# ssslidar_v0_1_main_board.net
KiCad netlist of a schematic drawn in EAGLE
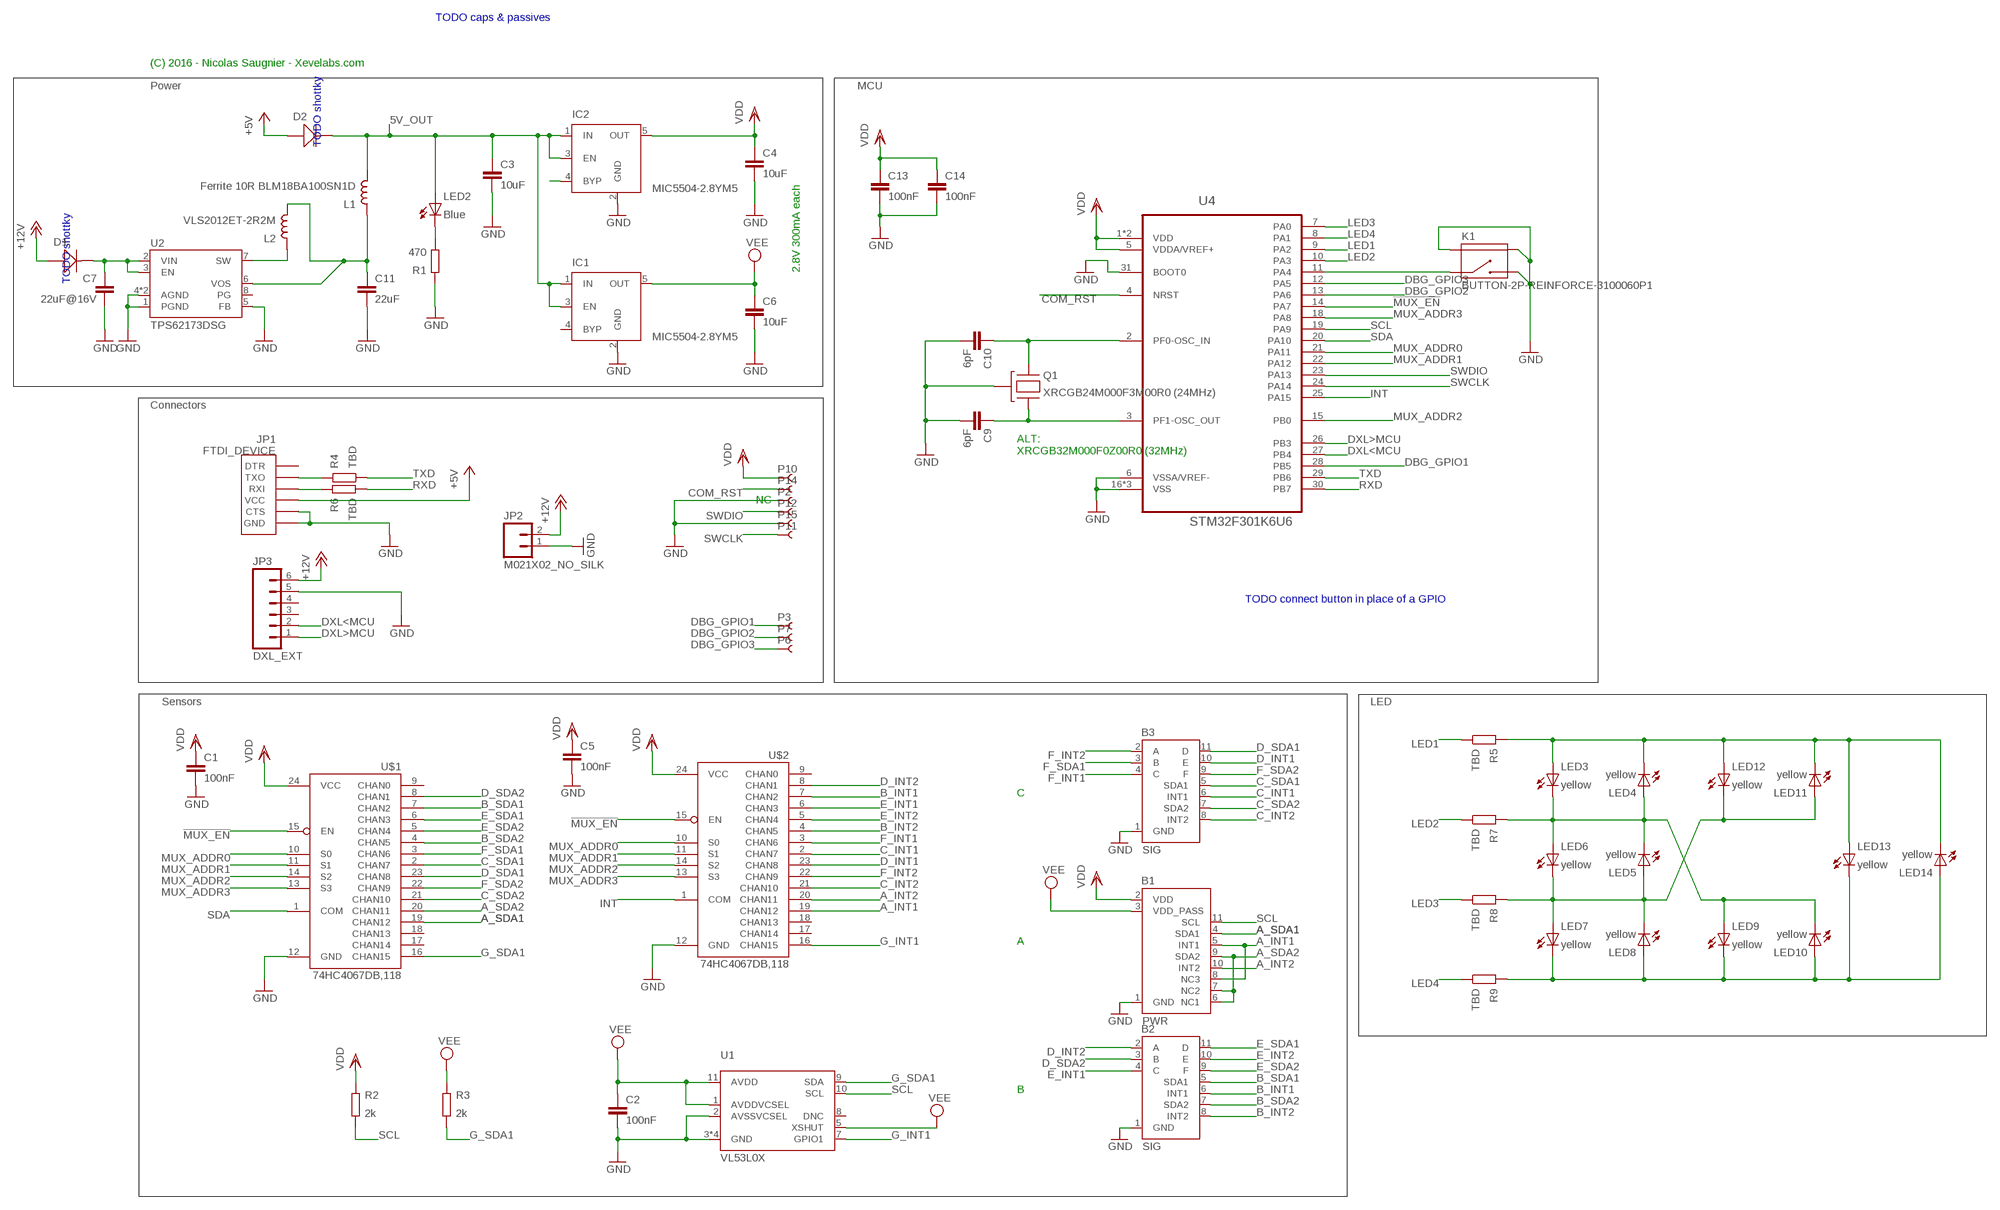
[diagram p0: schematic, sheet 1]

(export (version "E")
  (design (tool "Eeschema 10.0.6"))
  (components
    (comp (ref "B1")
      (value "PWR")
      (footprint "eagle-import:BLADE")
      (libsource (lib "eagle-import") (part "BLADE_PWR_BOTTOM"))
    )
    (comp (ref "B2")
      (value "SIG")
      (footprint "eagle-import:BLADE")
      (libsource (lib "eagle-import") (part "BLADE_SIG_BOTTOM"))
    )
    (comp (ref "B3")
      (value "SIG")
      (footprint "eagle-import:BLADE")
      (libsource (lib "eagle-import") (part "BLADE_SIG_BOTTOM"))
    )
    (comp (ref "C1")
      (value "100nF")
      (footprint "eagle-import:0402_N")
      (libsource (lib "eagle-import") (part "C0402"))
    )
    (comp (ref "C2")
      (value "100nF")
      (footprint "eagle-import:0402_N")
      (libsource (lib "eagle-import") (part "C0402"))
    )
    (comp (ref "C3")
      (value "10uF")
      (footprint "eagle-import:0805_N")
      (libsource (lib "eagle-import") (part "C0805"))
    )
    (comp (ref "C4")
      (value "10uF")
      (footprint "eagle-import:0805_N")
      (libsource (lib "eagle-import") (part "C0805"))
    )
    (comp (ref "C5")
      (value "100nF")
      (footprint "eagle-import:0402_N")
      (libsource (lib "eagle-import") (part "C0402"))
    )
    (comp (ref "C6")
      (value "10uF")
      (footprint "eagle-import:0805_N")
      (libsource (lib "eagle-import") (part "C0805"))
    )
    (comp (ref "C7")
      (value "22uF@16V")
      (footprint "eagle-import:1206_L")
      (libsource (lib "eagle-import") (part "C1206_L"))
    )
    (comp (ref "C9")
      (value "6pF")
      (footprint "eagle-import:0402_N")
      (libsource (lib "eagle-import") (part "C0402"))
    )
    (comp (ref "C10")
      (value "6pF")
      (footprint "eagle-import:0402_N")
      (libsource (lib "eagle-import") (part "C0402"))
    )
    (comp (ref "C11")
      (value "22uF")
      (footprint "eagle-import:1206_L")
      (libsource (lib "eagle-import") (part "C1206_L"))
    )
    (comp (ref "C13")
      (value "100nF")
      (footprint "eagle-import:0402_N")
      (libsource (lib "eagle-import") (part "C0402"))
    )
    (comp (ref "C14")
      (value "100nF")
      (footprint "eagle-import:0402_N")
      (libsource (lib "eagle-import") (part "C0402"))
    )
    (comp (ref "D1")
      (value "D-SOD-123")
      (footprint "eagle-import:SOD123")
      (libsource (lib "eagle-import") (part "D-SOD-123"))
    )
    (comp (ref "D2")
      (value "D-SOD-123")
      (footprint "eagle-import:SOD123")
      (libsource (lib "eagle-import") (part "D-SOD-123"))
    )
    (comp (ref "IC1")
      (value "MIC5504-2.8YM5")
      (footprint "eagle-import:SOT23-5")
      (libsource (lib "eagle-import") (part "MIC5219XX"))
    )
    (comp (ref "IC2")
      (value "MIC5504-2.8YM5")
      (footprint "eagle-import:SOT23-5")
      (libsource (lib "eagle-import") (part "MIC5219XX"))
    )
    (comp (ref "JP1")
      (value "FTDI_DEVICE")
      (footprint "eagle-import:FTDI_DEVICE_SIDE")
      (libsource (lib "eagle-import") (part "FTDI_DEVICE"))
    )
    (comp (ref "JP2")
      (value "M021X02_NO_SILK")
      (footprint "eagle-import:1X02_NO_SILK")
      (libsource (lib "eagle-import") (part "M021X02_NO_SILK"))
    )
    (comp (ref "JP3")
      (value "DXL_EXT")
      (footprint "eagle-import:1X06-1.27MM")
      (libsource (lib "eagle-import") (part "M061.27MM"))
    )
    (comp (ref "K1")
      (value "BUTTON-2P-REINFORCE-3100060P1")
      (footprint "eagle-import:4P-SMD-7.0X3.5X3.5H-90D")
      (libsource (lib "eagle-import") (part "BUTTON-2P-REINFORCE-3100060P1"))
    )
    (comp (ref "L1")
      (value "Ferrite 10R BLM18BA100SN1D")
      (footprint "eagle-import:0603_N")
      (libsource (lib "eagle-import") (part "L0603"))
    )
    (comp (ref "L2")
      (value "VLS2012ET-2R2M")
      (footprint "eagle-import:2016_METRIC_N")
      (libsource (lib "eagle-import") (part "L2016M"))
    )
    (comp (ref "LED2")
      (value "Blue")
      (footprint "eagle-import:D_0603_N")
      (libsource (lib "eagle-import") (part "LED0603"))
    )
    (comp (ref "LED3")
      (value "yellow")
      (footprint "eagle-import:D_0603_N")
      (libsource (lib "eagle-import") (part "LED0603"))
    )
    (comp (ref "LED4")
      (value "yellow")
      (footprint "eagle-import:D_0603_N")
      (libsource (lib "eagle-import") (part "LED0603"))
    )
    (comp (ref "LED5")
      (value "yellow")
      (footprint "eagle-import:D_0603_N")
      (libsource (lib "eagle-import") (part "LED0603"))
    )
    (comp (ref "LED6")
      (value "yellow")
      (footprint "eagle-import:D_0603_N")
      (libsource (lib "eagle-import") (part "LED0603"))
    )
    (comp (ref "LED7")
      (value "yellow")
      (footprint "eagle-import:D_0603_N")
      (libsource (lib "eagle-import") (part "LED0603"))
    )
    (comp (ref "LED8")
      (value "yellow")
      (footprint "eagle-import:D_0603_N")
      (libsource (lib "eagle-import") (part "LED0603"))
    )
    (comp (ref "LED9")
      (value "yellow")
      (footprint "eagle-import:D_0603_N")
      (libsource (lib "eagle-import") (part "LED0603"))
    )
    (comp (ref "LED10")
      (value "yellow")
      (footprint "eagle-import:D_0603_N")
      (libsource (lib "eagle-import") (part "LED0603"))
    )
    (comp (ref "LED11")
      (value "yellow")
      (footprint "eagle-import:D_0603_N")
      (libsource (lib "eagle-import") (part "LED0603"))
    )
    (comp (ref "LED12")
      (value "yellow")
      (footprint "eagle-import:D_0603_N")
      (libsource (lib "eagle-import") (part "LED0603"))
    )
    (comp (ref "LED13")
      (value "yellow")
      (footprint "eagle-import:D_0603_N")
      (libsource (lib "eagle-import") (part "LED0603"))
    )
    (comp (ref "LED14")
      (value "yellow")
      (footprint "eagle-import:D_0603_N")
      (libsource (lib "eagle-import") (part "LED0603"))
    )
    (comp (ref "P2")
      (value "PIN_SMD_1X1.6")
      (footprint "eagle-import:PIN_SMD_1X1.6")
      (libsource (lib "eagle-import") (part "PIN_SMD_1X1.6"))
    )
    (comp (ref "P3")
      (value "PIN_SMD_1X1")
      (footprint "eagle-import:PIN_SMD_1X1")
      (libsource (lib "eagle-import") (part "PIN_SMD_1X1"))
    )
    (comp (ref "P6")
      (value "PIN_SMD_1X1")
      (footprint "eagle-import:PIN_SMD_1X1")
      (libsource (lib "eagle-import") (part "PIN_SMD_1X1"))
    )
    (comp (ref "P7")
      (value "PIN_SMD_1X1")
      (footprint "eagle-import:PIN_SMD_1X1")
      (libsource (lib "eagle-import") (part "PIN_SMD_1X1"))
    )
    (comp (ref "P10")
      (value "PIN_SMD_1X1.6")
      (footprint "eagle-import:PIN_SMD_1X1.6")
      (libsource (lib "eagle-import") (part "PIN_SMD_1X1.6"))
    )
    (comp (ref "P11")
      (value "PIN_SMD_1X1.6")
      (footprint "eagle-import:PIN_SMD_1X1.6")
      (libsource (lib "eagle-import") (part "PIN_SMD_1X1.6"))
    )
    (comp (ref "P12")
      (value "PIN_SMD_1X1.6")
      (footprint "eagle-import:PIN_SMD_1X1.6")
      (libsource (lib "eagle-import") (part "PIN_SMD_1X1.6"))
    )
    (comp (ref "P14")
      (value "PIN_SMD_1X1.6")
      (footprint "eagle-import:PIN_SMD_1X1.6")
      (libsource (lib "eagle-import") (part "PIN_SMD_1X1.6"))
    )
    (comp (ref "P15")
      (value "PIN_SMD_1X1.6")
      (footprint "eagle-import:PIN_SMD_1X1.6")
      (libsource (lib "eagle-import") (part "PIN_SMD_1X1.6"))
    )
    (comp (ref "Q1")
      (value "XRCGB24M000F3M00R0 (24MHz)")
      (footprint "eagle-import:CRYSTAL_2.0X1.6_4P")
      (libsource (lib "eagle-import") (part "CRYSTAL_W/BODY-2.0X1.6"))
    )
    (comp (ref "R1")
      (value "470")
      (footprint "eagle-import:0402_N")
      (libsource (lib "eagle-import") (part "R0402"))
    )
    (comp (ref "R2")
      (value "2k")
      (footprint "eagle-import:0402_N")
      (libsource (lib "eagle-import") (part "R0402"))
    )
    (comp (ref "R3")
      (value "2k")
      (footprint "eagle-import:0402_N")
      (libsource (lib "eagle-import") (part "R0402"))
    )
    (comp (ref "R4")
      (value "TBD")
      (footprint "eagle-import:0402_N")
      (libsource (lib "eagle-import") (part "R0402"))
    )
    (comp (ref "R5")
      (value "TBD")
      (footprint "eagle-import:0402_N")
      (libsource (lib "eagle-import") (part "R0402"))
    )
    (comp (ref "R6")
      (value "TBD")
      (footprint "eagle-import:0402_N")
      (libsource (lib "eagle-import") (part "R0402"))
    )
    (comp (ref "R7")
      (value "TBD")
      (footprint "eagle-import:0402_N")
      (libsource (lib "eagle-import") (part "R0402"))
    )
    (comp (ref "R8")
      (value "TBD")
      (footprint "eagle-import:0402_N")
      (libsource (lib "eagle-import") (part "R0402"))
    )
    (comp (ref "R9")
      (value "TBD")
      (footprint "eagle-import:0402_N")
      (libsource (lib "eagle-import") (part "R0402"))
    )
    (comp (ref "U$1")
      (value "74HC4067DB,118")
      (footprint "eagle-import:SSOP24")
      (libsource (lib "eagle-import") (part "MUX-74HC4067SMD"))
    )
    (comp (ref "U$2")
      (value "74HC4067DB,118")
      (footprint "eagle-import:SSOP24")
      (libsource (lib "eagle-import") (part "MUX-74HC4067SMD"))
    )
    (comp (ref "U1")
      (value "VL53L0X")
      (footprint "eagle-import:VL53L0X")
      (libsource (lib "eagle-import") (part "VL53L0X"))
    )
    (comp (ref "U2")
      (value "TPS62173DSG")
      (footprint "eagle-import:SON50P200X200X80-9N")
      (libsource (lib "eagle-import") (part "IC_TPS62160DSG_N"))
    )
    (comp (ref "U4")
      (value "STM32F301K6U6")
      (footprint "eagle-import:QFN50P500X500X60-33N")
      (fields (field (name "MPN") "STM32F050K4U6A"))
      (libsource (lib "eagle-import") (part "STM32F301K6U6"))
    )
  )
  (nets
    (net (code "1") (name "+5V") (class "Default")
      (node (ref "D2") (pin "+") (pinfunction "+_+") (pintype "passive"))
      (node (ref "JP1") (pin "P$4") (pinfunction "VCC_P$4") (pintype "bidirectional"))
    )
    (net (code "2") (name "+12V") (class "Default")
      (node (ref "D1") (pin "+") (pinfunction "+_+") (pintype "passive"))
      (node (ref "JP2") (pin "2") (pinfunction "2_2") (pintype "passive"))
      (node (ref "JP3") (pin "6") (pinfunction "6_6") (pintype "passive"))
    )
    (net (code "3") (name "/5V_OUT") (class "Default")
      (node (ref "C3") (pin "1") (pinfunction "1_1") (pintype "passive"))
      (node (ref "D2") (pin "-") (pinfunction "-_-") (pintype "passive"))
      (node (ref "IC1") (pin "1") (pinfunction "IN_1") (pintype "input"))
      (node (ref "IC1") (pin "3") (pinfunction "EN_3") (pintype "input"))
      (node (ref "IC2") (pin "1") (pinfunction "IN_1") (pintype "input"))
      (node (ref "IC2") (pin "3") (pinfunction "EN_3") (pintype "input"))
      (node (ref "L1") (pin "2") (pinfunction "2_2") (pintype "passive"))
      (node (ref "LED2") (pin "A") (pinfunction "A_A") (pintype "passive"))
    )
    (net (code "4") (name "/A_INT1") (class "Default")
      (node (ref "B1") (pin "5") (pinfunction "INT1_5") (pintype "bidirectional"))
      (node (ref "B1") (pin "8") (pinfunction "NC3_8") (pintype "bidirectional"))
      (node (ref "U$2") (pin "19") (pinfunction "CHAN12_19") (pintype "bidirectional"))
    )
    (net (code "5") (name "/A_INT2") (class "Default")
      (node (ref "B1") (pin "10") (pinfunction "INT2_10") (pintype "bidirectional"))
      (node (ref "U$2") (pin "20") (pinfunction "CHAN11_20") (pintype "bidirectional"))
    )
    (net (code "6") (name "/A_SDA1") (class "Default")
      (node (ref "B1") (pin "4") (pinfunction "SDA1_4") (pintype "bidirectional"))
      (node (ref "U$1") (pin "19") (pinfunction "CHAN12_19") (pintype "bidirectional"))
    )
    (net (code "7") (name "/A_SDA2") (class "Default")
      (node (ref "B1") (pin "6") (pinfunction "NC1_6") (pintype "bidirectional"))
      (node (ref "B1") (pin "7") (pinfunction "NC2_7") (pintype "bidirectional"))
      (node (ref "B1") (pin "9") (pinfunction "SDA2_9") (pintype "bidirectional"))
      (node (ref "U$1") (pin "20") (pinfunction "CHAN11_20") (pintype "bidirectional"))
    )
    (net (code "8") (name "/B_INT1") (class "Default")
      (node (ref "B2") (pin "6") (pinfunction "INT1_6") (pintype "bidirectional"))
      (node (ref "U$2") (pin "7") (pinfunction "CHAN2_7") (pintype "bidirectional"))
    )
    (net (code "9") (name "/B_INT2") (class "Default")
      (node (ref "B2") (pin "8") (pinfunction "INT2_8") (pintype "bidirectional"))
      (node (ref "U$2") (pin "4") (pinfunction "CHAN5_4") (pintype "bidirectional"))
    )
    (net (code "10") (name "/B_SDA1") (class "Default")
      (node (ref "B2") (pin "5") (pinfunction "SDA1_5") (pintype "bidirectional"))
      (node (ref "U$1") (pin "7") (pinfunction "CHAN2_7") (pintype "bidirectional"))
    )
    (net (code "11") (name "/B_SDA2") (class "Default")
      (node (ref "B2") (pin "7") (pinfunction "SDA2_7") (pintype "bidirectional"))
      (node (ref "U$1") (pin "4") (pinfunction "CHAN5_4") (pintype "bidirectional"))
    )
    (net (code "12") (name "/COM_RST") (class "Default")
      (node (ref "P14") (pin "PIN") (pinfunction "1_PIN") (pintype "bidirectional"))
      (node (ref "U4") (pin "4") (pinfunction "NRST_4") (pintype "bidirectional"))
    )
    (net (code "13") (name "/C_INT1") (class "Default")
      (node (ref "B3") (pin "6") (pinfunction "INT1_6") (pintype "bidirectional"))
      (node (ref "U$2") (pin "2") (pinfunction "CHAN7_2") (pintype "bidirectional"))
    )
    (net (code "14") (name "/C_INT2") (class "Default")
      (node (ref "B3") (pin "8") (pinfunction "INT2_8") (pintype "bidirectional"))
      (node (ref "U$2") (pin "21") (pinfunction "CHAN10_21") (pintype "bidirectional"))
    )
    (net (code "15") (name "/C_SDA1") (class "Default")
      (node (ref "B3") (pin "5") (pinfunction "SDA1_5") (pintype "bidirectional"))
      (node (ref "U$1") (pin "2") (pinfunction "CHAN7_2") (pintype "bidirectional"))
    )
    (net (code "16") (name "/C_SDA2") (class "Default")
      (node (ref "B3") (pin "7") (pinfunction "SDA2_7") (pintype "bidirectional"))
      (node (ref "U$1") (pin "21") (pinfunction "CHAN10_21") (pintype "bidirectional"))
    )
    (net (code "17") (name "/DBG_GPIO1") (class "Default")
      (node (ref "P3") (pin "P$1") (pinfunction "1_P$1") (pintype "bidirectional"))
      (node (ref "U4") (pin "28") (pinfunction "PB5_28") (pintype "bidirectional"))
    )
    (net (code "18") (name "/DBG_GPIO2") (class "Default")
      (node (ref "P7") (pin "P$1") (pinfunction "1_P$1") (pintype "bidirectional"))
      (node (ref "U4") (pin "13") (pinfunction "PA6_13") (pintype "bidirectional"))
    )
    (net (code "19") (name "/DBG_GPIO3") (class "Default")
      (node (ref "P6") (pin "P$1") (pinfunction "1_P$1") (pintype "bidirectional"))
      (node (ref "U4") (pin "12") (pinfunction "PA5_12") (pintype "bidirectional"))
    )
    (net (code "20") (name "/DXL<MCU") (class "Default")
      (node (ref "JP3") (pin "2") (pinfunction "2_2") (pintype "passive"))
      (node (ref "U4") (pin "27") (pinfunction "PB4_27") (pintype "bidirectional"))
    )
    (net (code "21") (name "/DXL>MCU") (class "Default")
      (node (ref "JP3") (pin "1") (pinfunction "1_1") (pintype "passive"))
      (node (ref "U4") (pin "26") (pinfunction "PB3_26") (pintype "bidirectional"))
    )
    (net (code "22") (name "/D_INT1") (class "Default")
      (node (ref "B3") (pin "10") (pinfunction "E_10") (pintype "bidirectional"))
      (node (ref "U$2") (pin "23") (pinfunction "CHAN8_23") (pintype "bidirectional"))
    )
    (net (code "23") (name "/D_INT2") (class "Default")
      (node (ref "B2") (pin "2") (pinfunction "A_2") (pintype "bidirectional"))
      (node (ref "U$2") (pin "8") (pinfunction "CHAN1_8") (pintype "bidirectional"))
    )
    (net (code "24") (name "/D_SDA1") (class "Default")
      (node (ref "B3") (pin "11") (pinfunction "D_11") (pintype "bidirectional"))
      (node (ref "U$1") (pin "23") (pinfunction "CHAN8_23") (pintype "bidirectional"))
    )
    (net (code "25") (name "/D_SDA2") (class "Default")
      (node (ref "B2") (pin "3") (pinfunction "B_3") (pintype "bidirectional"))
      (node (ref "U$1") (pin "8") (pinfunction "CHAN1_8") (pintype "bidirectional"))
    )
    (net (code "26") (name "/E_INT1") (class "Default")
      (node (ref "B2") (pin "4") (pinfunction "C_4") (pintype "bidirectional"))
      (node (ref "U$2") (pin "6") (pinfunction "CHAN3_6") (pintype "bidirectional"))
    )
    (net (code "27") (name "/E_INT2") (class "Default")
      (node (ref "B2") (pin "10") (pinfunction "E_10") (pintype "bidirectional"))
      (node (ref "U$2") (pin "5") (pinfunction "CHAN4_5") (pintype "bidirectional"))
    )
    (net (code "28") (name "/E_SDA1") (class "Default")
      (node (ref "B2") (pin "11") (pinfunction "D_11") (pintype "bidirectional"))
      (node (ref "U$1") (pin "6") (pinfunction "CHAN3_6") (pintype "bidirectional"))
    )
    (net (code "29") (name "/E_SDA2") (class "Default")
      (node (ref "B2") (pin "9") (pinfunction "F_9") (pintype "bidirectional"))
      (node (ref "U$1") (pin "5") (pinfunction "CHAN4_5") (pintype "bidirectional"))
    )
    (net (code "30") (name "/F_INT1") (class "Default")
      (node (ref "B3") (pin "4") (pinfunction "C_4") (pintype "bidirectional"))
      (node (ref "U$2") (pin "3") (pinfunction "CHAN6_3") (pintype "bidirectional"))
    )
    (net (code "31") (name "/F_INT2") (class "Default")
      (node (ref "B3") (pin "2") (pinfunction "A_2") (pintype "bidirectional"))
      (node (ref "U$2") (pin "22") (pinfunction "CHAN9_22") (pintype "bidirectional"))
    )
    (net (code "32") (name "/F_SDA1") (class "Default")
      (node (ref "B3") (pin "3") (pinfunction "B_3") (pintype "bidirectional"))
      (node (ref "U$1") (pin "3") (pinfunction "CHAN6_3") (pintype "bidirectional"))
    )
    (net (code "33") (name "/F_SDA2") (class "Default")
      (node (ref "B3") (pin "9") (pinfunction "F_9") (pintype "bidirectional"))
      (node (ref "U$1") (pin "22") (pinfunction "CHAN9_22") (pintype "bidirectional"))
    )
    (net (code "34") (name "/G_INT1") (class "Default")
      (node (ref "U$2") (pin "16") (pinfunction "CHAN15_16") (pintype "bidirectional"))
      (node (ref "U1") (pin "7") (pinfunction "GPIO1_7") (pintype "bidirectional"))
    )
    (net (code "35") (name "/G_SDA1") (class "Default")
      (node (ref "R3") (pin "1") (pinfunction "1_1") (pintype "passive"))
      (node (ref "U$1") (pin "16") (pinfunction "CHAN15_16") (pintype "bidirectional"))
      (node (ref "U1") (pin "9") (pinfunction "SDA_9") (pintype "bidirectional"))
    )
    (net (code "36") (name "/INT") (class "Default")
      (node (ref "U$2") (pin "1") (pinfunction "COM_1") (pintype "bidirectional"))
      (node (ref "U4") (pin "25") (pinfunction "PA15_25") (pintype "bidirectional"))
    )
    (net (code "37") (name "/LED1") (class "Default")
      (node (ref "R5") (pin "1") (pinfunction "1_1") (pintype "passive"))
      (node (ref "U4") (pin "9") (pinfunction "PA2_9") (pintype "bidirectional"))
    )
    (net (code "38") (name "/LED2") (class "Default")
      (node (ref "R7") (pin "1") (pinfunction "1_1") (pintype "passive"))
      (node (ref "U4") (pin "10") (pinfunction "PA3_10") (pintype "bidirectional"))
    )
    (net (code "39") (name "/LED3") (class "Default")
      (node (ref "R8") (pin "1") (pinfunction "1_1") (pintype "passive"))
      (node (ref "U4") (pin "7") (pinfunction "PA0_7") (pintype "bidirectional"))
    )
    (net (code "40") (name "/LED4") (class "Default")
      (node (ref "R9") (pin "1") (pinfunction "1_1") (pintype "passive"))
      (node (ref "U4") (pin "8") (pinfunction "PA1_8") (pintype "bidirectional"))
    )
    (net (code "41") (name "/MUX_ADDR0") (class "Default")
      (node (ref "U$1") (pin "10") (pinfunction "S0_10") (pintype "input"))
      (node (ref "U$2") (pin "10") (pinfunction "S0_10") (pintype "input"))
      (node (ref "U4") (pin "21") (pinfunction "PA11_21") (pintype "bidirectional"))
    )
    (net (code "42") (name "/MUX_ADDR1") (class "Default")
      (node (ref "U$1") (pin "11") (pinfunction "S1_11") (pintype "input"))
      (node (ref "U$2") (pin "11") (pinfunction "S1_11") (pintype "input"))
      (node (ref "U4") (pin "22") (pinfunction "PA12_22") (pintype "bidirectional"))
    )
    (net (code "43") (name "/MUX_ADDR2") (class "Default")
      (node (ref "U$1") (pin "14") (pinfunction "S2_14") (pintype "input"))
      (node (ref "U$2") (pin "14") (pinfunction "S2_14") (pintype "input"))
      (node (ref "U4") (pin "15") (pinfunction "PB0_15") (pintype "bidirectional"))
    )
    (net (code "44") (name "/MUX_ADDR3") (class "Default")
      (node (ref "U$1") (pin "13") (pinfunction "S3_13") (pintype "input"))
      (node (ref "U$2") (pin "13") (pinfunction "S3_13") (pintype "input"))
      (node (ref "U4") (pin "18") (pinfunction "PA8_18") (pintype "bidirectional"))
    )
    (net (code "45") (name "/RXD") (class "Default")
      (node (ref "R6") (pin "1") (pinfunction "1_1") (pintype "passive"))
      (node (ref "U4") (pin "30") (pinfunction "PB7_30") (pintype "bidirectional"))
    )
    (net (code "46") (name "/SCL") (class "Default")
      (node (ref "B1") (pin "11") (pinfunction "SCL_11") (pintype "bidirectional"))
      (node (ref "R2") (pin "1") (pinfunction "1_1") (pintype "passive"))
      (node (ref "U1") (pin "10") (pinfunction "SCL_10") (pintype "bidirectional"))
      (node (ref "U4") (pin "19") (pinfunction "PA9_19") (pintype "bidirectional"))
    )
    (net (code "47") (name "/SDA") (class "Default")
      (node (ref "U$1") (pin "1") (pinfunction "COM_1") (pintype "bidirectional"))
      (node (ref "U4") (pin "20") (pinfunction "PA10_20") (pintype "bidirectional"))
    )
    (net (code "48") (name "/SWCLK") (class "Default")
      (node (ref "P11") (pin "PIN") (pinfunction "1_PIN") (pintype "bidirectional"))
      (node (ref "U4") (pin "24") (pinfunction "PA14_24") (pintype "bidirectional"))
    )
    (net (code "49") (name "/SWDIO") (class "Default")
      (node (ref "P12") (pin "PIN") (pinfunction "1_PIN") (pintype "bidirectional"))
      (node (ref "U4") (pin "23") (pinfunction "PA13_23") (pintype "bidirectional"))
    )
    (net (code "50") (name "/TXD") (class "Default")
      (node (ref "R4") (pin "1") (pinfunction "1_1") (pintype "passive"))
      (node (ref "U4") (pin "29") (pinfunction "PB6_29") (pintype "bidirectional"))
    )
    (net (code "51") (name "/~{MUX_EN}") (class "Default")
      (node (ref "U$1") (pin "15") (pinfunction "EN_15") (pintype "input"))
      (node (ref "U$2") (pin "15") (pinfunction "EN_15") (pintype "input"))
      (node (ref "U4") (pin "14") (pinfunction "PA7_14") (pintype "bidirectional"))
    )
    (net (code "52") (name "GND") (class "Default")
      (node (ref "B1") (pin "1") (pinfunction "GND_1") (pintype "bidirectional"))
      (node (ref "B2") (pin "1") (pinfunction "GND_1") (pintype "bidirectional"))
      (node (ref "B3") (pin "1") (pinfunction "GND_1") (pintype "bidirectional"))
      (node (ref "C1") (pin "2") (pinfunction "2_2") (pintype "passive"))
      (node (ref "C10") (pin "2") (pinfunction "2_2") (pintype "passive"))
      (node (ref "C11") (pin "2") (pinfunction "2_2") (pintype "passive"))
      (node (ref "C13") (pin "2") (pinfunction "2_2") (pintype "passive"))
      (node (ref "C14") (pin "2") (pinfunction "2_2") (pintype "passive"))
      (node (ref "C2") (pin "2") (pinfunction "2_2") (pintype "passive"))
      (node (ref "C3") (pin "2") (pinfunction "2_2") (pintype "passive"))
      (node (ref "C4") (pin "2") (pinfunction "2_2") (pintype "passive"))
      (node (ref "C5") (pin "2") (pinfunction "2_2") (pintype "passive"))
      (node (ref "C6") (pin "2") (pinfunction "2_2") (pintype "passive"))
      (node (ref "C7") (pin "2") (pinfunction "2_2") (pintype "passive"))
      (node (ref "C9") (pin "2") (pinfunction "2_2") (pintype "passive"))
      (node (ref "IC1") (pin "2") (pinfunction "GND_2") (pintype "power_in"))
      (node (ref "IC2") (pin "2") (pinfunction "GND_2") (pintype "power_in"))
      (node (ref "JP1") (pin "P$5") (pinfunction "CTS_P$5") (pintype "bidirectional"))
      (node (ref "JP1") (pin "P$6") (pinfunction "GND_P$6") (pintype "bidirectional"))
      (node (ref "JP2") (pin "1") (pinfunction "1_1") (pintype "passive"))
      (node (ref "JP3") (pin "5") (pinfunction "5_5") (pintype "passive"))
      (node (ref "K1") (pin "2") (pinfunction "2_2") (pintype "bidirectional"))
      (node (ref "K1") (pin "S1") (pinfunction "S1_S1") (pintype "bidirectional"))
      (node (ref "K1") (pin "S2") (pinfunction "S2_S2") (pintype "bidirectional"))
      (node (ref "P15") (pin "PIN") (pinfunction "1_PIN") (pintype "bidirectional"))
      (node (ref "P2") (pin "PIN") (pinfunction "1_PIN") (pintype "bidirectional"))
      (node (ref "Q1") (pin "2") (pinfunction "GND_2") (pintype "passive"))
      (node (ref "Q1") (pin "4") (pinfunction "GND_4") (pintype "passive"))
      (node (ref "R1") (pin "2") (pinfunction "2_2") (pintype "passive"))
      (node (ref "U$1") (pin "12") (pinfunction "GND_12") (pintype "bidirectional"))
      (node (ref "U$2") (pin "12") (pinfunction "GND_12") (pintype "bidirectional"))
      (node (ref "U1") (pin "12") (pinfunction "GND_12") (pintype "bidirectional"))
      (node (ref "U1") (pin "2") (pinfunction "AVSSVCSEL_2") (pintype "bidirectional"))
      (node (ref "U1") (pin "3") (pinfunction "GND_3") (pintype "bidirectional"))
      (node (ref "U1") (pin "4") (pinfunction "GND_4") (pintype "bidirectional"))
      (node (ref "U1") (pin "6") (pinfunction "GND_6") (pintype "bidirectional"))
      (node (ref "U2") (pin "1") (pinfunction "PGND_1") (pintype "input"))
      (node (ref "U2") (pin "4") (pinfunction "AGND_4") (pintype "input"))
      (node (ref "U2") (pin "5") (pinfunction "FB_5") (pintype "bidirectional"))
      (node (ref "U2") (pin "9") (pinfunction "AGND_9") (pintype "input"))
      (node (ref "U4") (pin "16") (pinfunction "VSS_16") (pintype "bidirectional"))
      (node (ref "U4") (pin "31") (pinfunction "BOOT0_31") (pintype "input"))
      (node (ref "U4") (pin "32") (pinfunction "VSS_32") (pintype "bidirectional"))
      (node (ref "U4") (pin "33") (pinfunction "VSS_33") (pintype "bidirectional"))
      (node (ref "U4") (pin "6") (pinfunction "VSSA/VREF-_6") (pintype "passive"))
    )
    (net (code "53") (name "Net-(JP1-RXI)") (class "Default")
      (node (ref "JP1") (pin "P$3") (pinfunction "RXI_P$3") (pintype "bidirectional"))
      (node (ref "R6") (pin "2") (pinfunction "2_2") (pintype "passive"))
    )
    (net (code "54") (name "Net-(JP1-TXO)") (class "Default")
      (node (ref "JP1") (pin "P$2") (pinfunction "TXO_P$2") (pintype "bidirectional"))
      (node (ref "R4") (pin "2") (pinfunction "2_2") (pintype "passive"))
    )
    (net (code "55") (name "Net-(LED2-PadC)") (class "Default")
      (node (ref "LED2") (pin "C") (pinfunction "C_C") (pintype "passive"))
      (node (ref "R1") (pin "1") (pinfunction "1_1") (pintype "passive"))
    )
    (net (code "56") (name "Net-(LED10-PadA)") (class "Default")
      (node (ref "LED10") (pin "A") (pinfunction "A_A") (pintype "passive"))
      (node (ref "LED13") (pin "C") (pinfunction "C_C") (pintype "passive"))
      (node (ref "LED14") (pin "A") (pinfunction "A_A") (pintype "passive"))
      (node (ref "LED7") (pin "C") (pinfunction "C_C") (pintype "passive"))
      (node (ref "LED8") (pin "A") (pinfunction "A_A") (pintype "passive"))
      (node (ref "LED9") (pin "C") (pinfunction "C_C") (pintype "passive"))
      (node (ref "R9") (pin "2") (pinfunction "2_2") (pintype "passive"))
    )
    (net (code "57") (name "Net-(LED10-PadC)") (class "Default")
      (node (ref "LED10") (pin "C") (pinfunction "C_C") (pintype "passive"))
      (node (ref "LED3") (pin "C") (pinfunction "C_C") (pintype "passive"))
      (node (ref "LED4") (pin "A") (pinfunction "A_A") (pintype "passive"))
      (node (ref "LED5") (pin "C") (pinfunction "C_C") (pintype "passive"))
      (node (ref "LED6") (pin "A") (pinfunction "A_A") (pintype "passive"))
      (node (ref "LED9") (pin "A") (pinfunction "A_A") (pintype "passive"))
      (node (ref "R7") (pin "2") (pinfunction "2_2") (pintype "passive"))
    )
    (net (code "58") (name "Net-(LED11-PadA)") (class "Default")
      (node (ref "LED11") (pin "A") (pinfunction "A_A") (pintype "passive"))
      (node (ref "LED12") (pin "C") (pinfunction "C_C") (pintype "passive"))
      (node (ref "LED5") (pin "A") (pinfunction "A_A") (pintype "passive"))
      (node (ref "LED6") (pin "C") (pinfunction "C_C") (pintype "passive"))
      (node (ref "LED7") (pin "A") (pinfunction "A_A") (pintype "passive"))
      (node (ref "LED8") (pin "C") (pinfunction "C_C") (pintype "passive"))
      (node (ref "R8") (pin "2") (pinfunction "2_2") (pintype "passive"))
    )
    (net (code "59") (name "Net-(LED11-PadC)") (class "Default")
      (node (ref "LED11") (pin "C") (pinfunction "C_C") (pintype "passive"))
      (node (ref "LED12") (pin "A") (pinfunction "A_A") (pintype "passive"))
      (node (ref "LED13") (pin "A") (pinfunction "A_A") (pintype "passive"))
      (node (ref "LED14") (pin "C") (pinfunction "C_C") (pintype "passive"))
      (node (ref "LED3") (pin "A") (pinfunction "A_A") (pintype "passive"))
      (node (ref "LED4") (pin "C") (pinfunction "C_C") (pintype "passive"))
      (node (ref "R5") (pin "2") (pinfunction "2_2") (pintype "passive"))
    )
    (net (code "60") (name "Net-(Q1-P$1)") (class "Default")
      (node (ref "C10") (pin "1") (pinfunction "1_1") (pintype "passive"))
      (node (ref "Q1") (pin "1") (pinfunction "P$1_1") (pintype "passive"))
      (node (ref "U4") (pin "2") (pinfunction "PF0-OSC_IN_2") (pintype "bidirectional"))
    )
    (net (code "61") (name "Net-(Q1-P$2)") (class "Default")
      (node (ref "C9") (pin "1") (pinfunction "1_1") (pintype "passive"))
      (node (ref "Q1") (pin "3") (pinfunction "P$2_3") (pintype "passive"))
      (node (ref "U4") (pin "3") (pinfunction "PF1-OSC_OUT_3") (pintype "bidirectional"))
    )
    (net (code "62") (name "Net-(U2-EN)") (class "Default")
      (node (ref "C7") (pin "1") (pinfunction "1_1") (pintype "passive"))
      (node (ref "D1") (pin "-") (pinfunction "-_-") (pintype "passive"))
      (node (ref "U2") (pin "2") (pinfunction "VIN_2") (pintype "bidirectional"))
      (node (ref "U2") (pin "3") (pinfunction "EN_3") (pintype "input"))
    )
    (net (code "63") (name "Net-(U2-SW)") (class "Default")
      (node (ref "L2") (pin "1") (pinfunction "1_1") (pintype "passive"))
      (node (ref "U2") (pin "7") (pinfunction "SW_7") (pintype "bidirectional"))
    )
    (net (code "64") (name "Net-(U2-VOS)") (class "Default")
      (node (ref "C11") (pin "1") (pinfunction "1_1") (pintype "passive"))
      (node (ref "L1") (pin "1") (pinfunction "1_1") (pintype "passive"))
      (node (ref "L2") (pin "2") (pinfunction "2_2") (pintype "passive"))
      (node (ref "U2") (pin "6") (pinfunction "VOS_6") (pintype "bidirectional"))
    )
    (net (code "65") (name "Net-(U4-PA4)") (class "Default")
      (node (ref "K1") (pin "1") (pinfunction "1_1") (pintype "bidirectional"))
      (node (ref "U4") (pin "11") (pinfunction "PA4_11") (pintype "bidirectional"))
    )
    (net (code "66") (name "VDD") (class "Default")
      (node (ref "B1") (pin "2") (pinfunction "VDD_2") (pintype "bidirectional"))
      (node (ref "C1") (pin "1") (pinfunction "1_1") (pintype "passive"))
      (node (ref "C13") (pin "1") (pinfunction "1_1") (pintype "passive"))
      (node (ref "C14") (pin "1") (pinfunction "1_1") (pintype "passive"))
      (node (ref "C4") (pin "1") (pinfunction "1_1") (pintype "passive"))
      (node (ref "C5") (pin "1") (pinfunction "1_1") (pintype "passive"))
      (node (ref "IC2") (pin "5") (pinfunction "OUT_5") (pintype "output"))
      (node (ref "P10") (pin "PIN") (pinfunction "1_PIN") (pintype "bidirectional"))
      (node (ref "R2") (pin "2") (pinfunction "2_2") (pintype "passive"))
      (node (ref "U$1") (pin "24") (pinfunction "VCC_24") (pintype "bidirectional"))
      (node (ref "U$2") (pin "24") (pinfunction "VCC_24") (pintype "bidirectional"))
      (node (ref "U4") (pin "1") (pinfunction "VDD_1") (pintype "power_in"))
      (node (ref "U4") (pin "17") (pinfunction "VDD_17") (pintype "power_in"))
      (node (ref "U4") (pin "5") (pinfunction "VDDA/VREF+_5") (pintype "power_in"))
    )
    (net (code "67") (name "VEE") (class "Default")
      (node (ref "B1") (pin "3") (pinfunction "VDD_PASS_3") (pintype "bidirectional"))
      (node (ref "C2") (pin "1") (pinfunction "1_1") (pintype "passive"))
      (node (ref "C6") (pin "1") (pinfunction "1_1") (pintype "passive"))
      (node (ref "IC1") (pin "5") (pinfunction "OUT_5") (pintype "output"))
      (node (ref "R3") (pin "2") (pinfunction "2_2") (pintype "passive"))
      (node (ref "U1") (pin "1") (pinfunction "AVDDVCSEL_1") (pintype "bidirectional"))
      (node (ref "U1") (pin "11") (pinfunction "AVDD_11") (pintype "bidirectional"))
      (node (ref "U1") (pin "5") (pinfunction "XSHUT_5") (pintype "bidirectional"))
    )
    (net (code "68") (name "unconnected-(IC1-BYP-Pad4)") (class "Default")
      (node (ref "IC1") (pin "4") (pinfunction "BYP_4") (pintype "passive"))
    )
    (net (code "69") (name "unconnected-(IC2-BYP-Pad4)") (class "Default")
      (node (ref "IC2") (pin "4") (pinfunction "BYP_4") (pintype "passive"))
    )
    (net (code "70") (name "unconnected-(JP1-DTR-PadP$1)") (class "Default")
      (node (ref "JP1") (pin "P$1") (pinfunction "DTR_P$1") (pintype "bidirectional"))
    )
    (net (code "71") (name "unconnected-(JP3-Pad3)") (class "Default")
      (node (ref "JP3") (pin "3") (pinfunction "3_3") (pintype "passive"))
    )
    (net (code "72") (name "unconnected-(JP3-Pad4)") (class "Default")
      (node (ref "JP3") (pin "4") (pinfunction "4_4") (pintype "passive"))
    )
    (net (code "73") (name "unconnected-(U$1-CHAN0-Pad9)") (class "Default")
      (node (ref "U$1") (pin "9") (pinfunction "CHAN0_9") (pintype "bidirectional"))
    )
    (net (code "74") (name "unconnected-(U$1-CHAN13-Pad18)") (class "Default")
      (node (ref "U$1") (pin "18") (pinfunction "CHAN13_18") (pintype "bidirectional"))
    )
    (net (code "75") (name "unconnected-(U$1-CHAN14-Pad17)") (class "Default")
      (node (ref "U$1") (pin "17") (pinfunction "CHAN14_17") (pintype "bidirectional"))
    )
    (net (code "76") (name "unconnected-(U$2-CHAN0-Pad9)") (class "Default")
      (node (ref "U$2") (pin "9") (pinfunction "CHAN0_9") (pintype "bidirectional"))
    )
    (net (code "77") (name "unconnected-(U$2-CHAN13-Pad18)") (class "Default")
      (node (ref "U$2") (pin "18") (pinfunction "CHAN13_18") (pintype "bidirectional"))
    )
    (net (code "78") (name "unconnected-(U$2-CHAN14-Pad17)") (class "Default")
      (node (ref "U$2") (pin "17") (pinfunction "CHAN14_17") (pintype "bidirectional"))
    )
    (net (code "79") (name "unconnected-(U1-DNC-Pad8)") (class "Default")
      (node (ref "U1") (pin "8") (pinfunction "DNC_8") (pintype "bidirectional"))
    )
    (net (code "80") (name "unconnected-(U2-PG-Pad8)") (class "Default")
      (node (ref "U2") (pin "8") (pinfunction "PG_8") (pintype "bidirectional"))
    )
  )
)
